# temp_new.net
KiCad netlist of a schematic drawn in EAGLE
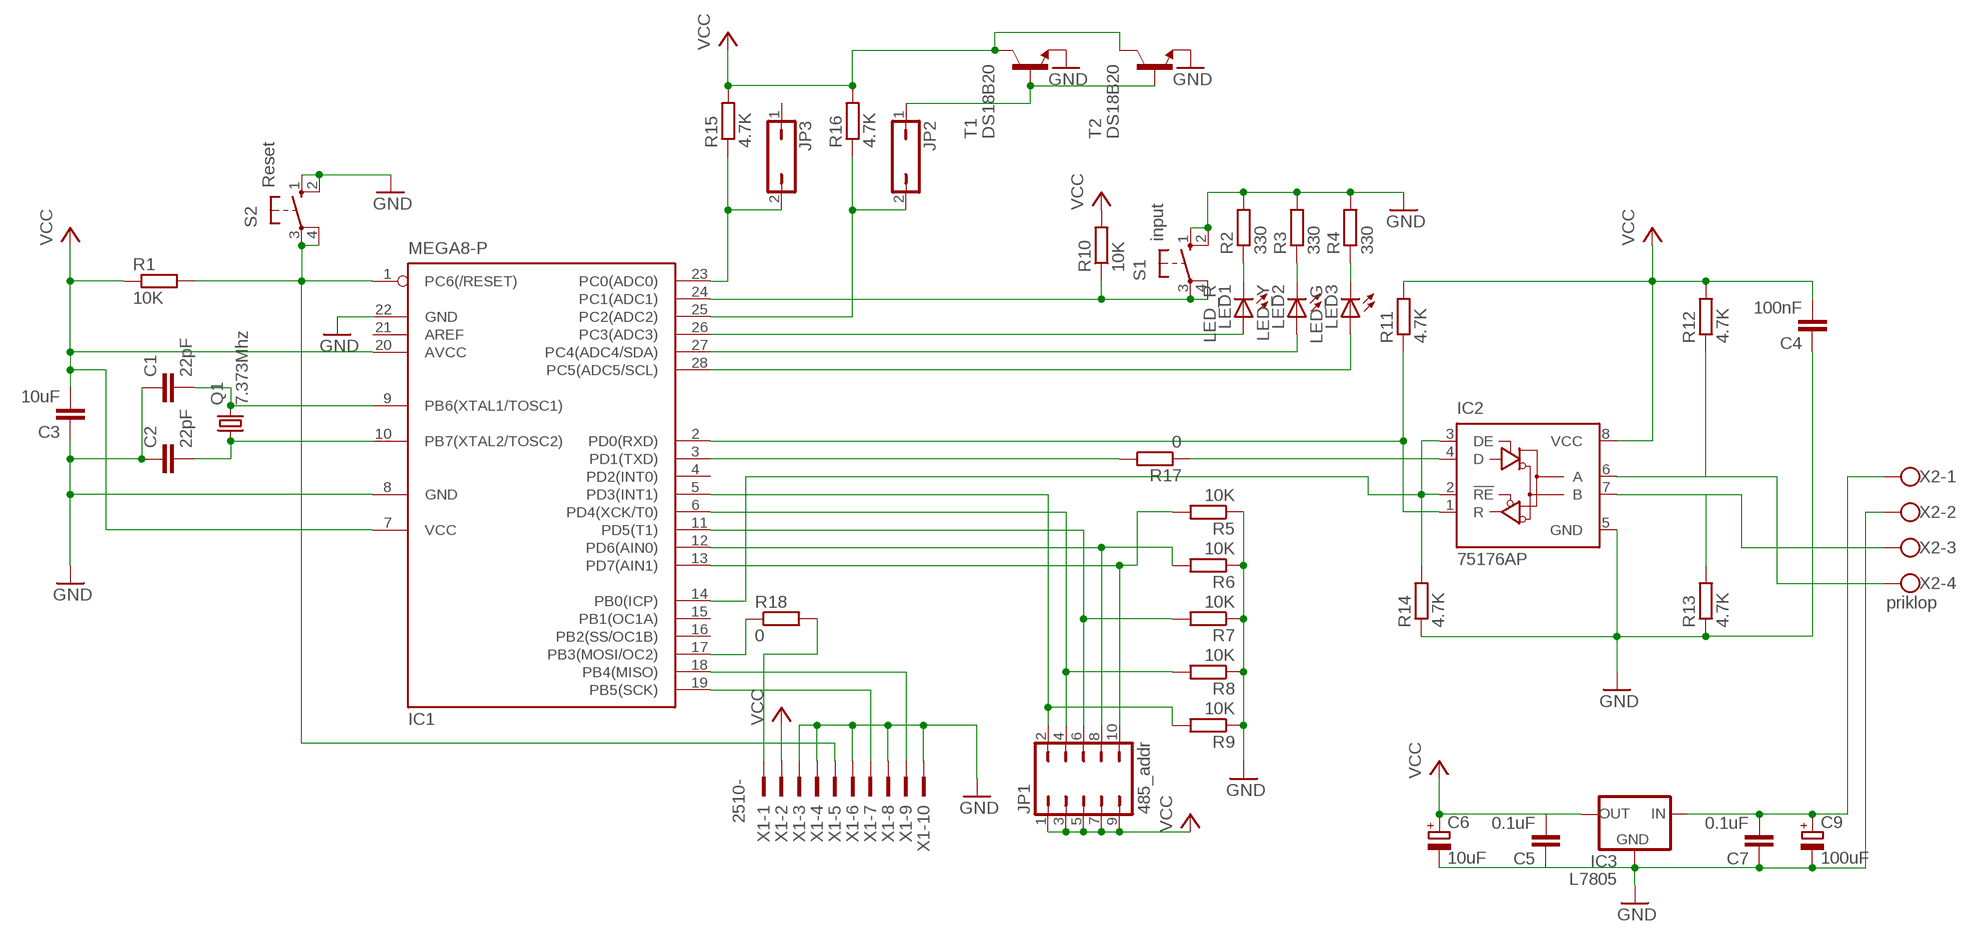
[diagram p0: schematic, sheet 1]

(export (version "E")
  (design (tool "Eeschema 10.0.6"))
  (components
    (comp (ref "C1")
      (value "22pF")
      (footprint "eagle-import:C025-030X050")
      (libsource (lib "eagle-import") (part "C-EU025-030X050"))
    )
    (comp (ref "C2")
      (value "22pF")
      (footprint "eagle-import:C025-030X050")
      (libsource (lib "eagle-import") (part "C-EU025-030X050"))
    )
    (comp (ref "C3")
      (value "10uF")
      (footprint "eagle-import:C025-030X050")
      (libsource (lib "eagle-import") (part "C-EU025-030X050"))
    )
    (comp (ref "C4")
      (value "100nF")
      (footprint "eagle-import:C025-030X050")
      (libsource (lib "eagle-import") (part "C-EU025-030X050"))
    )
    (comp (ref "C5")
      (value "0.1uF")
      (footprint "eagle-import:C025-030X050")
      (libsource (lib "eagle-import") (part "C-EU025-030X050"))
    )
    (comp (ref "C6")
      (value "10uF")
      (footprint "eagle-import:E2,5-6")
      (libsource (lib "eagle-import") (part "CPOL-EUE2.5-6"))
    )
    (comp (ref "C7")
      (value "0.1uF")
      (footprint "eagle-import:C025-030X050")
      (libsource (lib "eagle-import") (part "C-EU025-030X050"))
    )
    (comp (ref "C9")
      (value "100uF")
      (footprint "eagle-import:E5-13")
      (libsource (lib "eagle-import") (part "CPOL-EUE5-13"))
    )
    (comp (ref "IC1")
      (value "MEGA8-P")
      (footprint "eagle-import:DIL28-3")
      (libsource (lib "eagle-import") (part "MEGA8-P"))
    )
    (comp (ref "IC2")
      (value "75176AP")
      (footprint "eagle-import:DIL08")
      (libsource (lib "eagle-import") (part "75176AP"))
    )
    (comp (ref "IC3")
      (value "L7805")
      (footprint "eagle-import:78XXL")
      (libsource (lib "eagle-import") (part "78XXL"))
    )
    (comp (ref "JP1")
      (value "485_addr")
      (footprint "eagle-import:JP5Q")
      (libsource (lib "eagle-import") (part "JP5Q"))
    )
    (comp (ref "JP2")
      (value "JP1Q")
      (footprint "eagle-import:JP1")
      (libsource (lib "eagle-import") (part "JP1Q"))
    )
    (comp (ref "JP3")
      (value "JP1Q")
      (footprint "eagle-import:JP1")
      (libsource (lib "eagle-import") (part "JP1Q"))
    )
    (comp (ref "LED1")
      (value "LED_R")
      (footprint "eagle-import:LED3MM")
      (libsource (lib "eagle-import") (part "LED3MM"))
    )
    (comp (ref "LED2")
      (value "LED_Y")
      (footprint "eagle-import:LED3MM")
      (libsource (lib "eagle-import") (part "LED3MM"))
    )
    (comp (ref "LED3")
      (value "LED_G")
      (footprint "eagle-import:LED3MM")
      (libsource (lib "eagle-import") (part "LED3MM"))
    )
    (comp (ref "Q1")
      (value "7.373Mhz")
      (footprint "eagle-import:HC49_S")
      (libsource (lib "eagle-import") (part "CRYSTALHC49S"))
    )
    (comp (ref "R1")
      (value "10K")
      (footprint "eagle-import:0207_10")
      (libsource (lib "eagle-import") (part "R-EU_0207/10"))
    )
    (comp (ref "R2")
      (value "330")
      (footprint "eagle-import:0207_10")
      (libsource (lib "eagle-import") (part "R-EU_0207/10"))
    )
    (comp (ref "R3")
      (value "330")
      (footprint "eagle-import:0207_10")
      (libsource (lib "eagle-import") (part "R-EU_0207/10"))
    )
    (comp (ref "R4")
      (value "330")
      (footprint "eagle-import:0207_10")
      (libsource (lib "eagle-import") (part "R-EU_0207/10"))
    )
    (comp (ref "R5")
      (value "10K")
      (footprint "eagle-import:0207_10")
      (libsource (lib "eagle-import") (part "R-EU_0207/10"))
    )
    (comp (ref "R6")
      (value "10K")
      (footprint "eagle-import:0207_10")
      (libsource (lib "eagle-import") (part "R-EU_0207/10"))
    )
    (comp (ref "R7")
      (value "10K")
      (footprint "eagle-import:0207_10")
      (libsource (lib "eagle-import") (part "R-EU_0207/10"))
    )
    (comp (ref "R8")
      (value "10K")
      (footprint "eagle-import:0207_10")
      (libsource (lib "eagle-import") (part "R-EU_0207/10"))
    )
    (comp (ref "R9")
      (value "10K")
      (footprint "eagle-import:0207_10")
      (libsource (lib "eagle-import") (part "R-EU_0207/10"))
    )
    (comp (ref "R10")
      (value "10K")
      (footprint "eagle-import:0207_10")
      (libsource (lib "eagle-import") (part "R-EU_0207/10"))
    )
    (comp (ref "R11")
      (value "4.7K")
      (footprint "eagle-import:0207_10")
      (libsource (lib "eagle-import") (part "R-EU_0207/10"))
    )
    (comp (ref "R12")
      (value "4.7K")
      (footprint "eagle-import:0207_10")
      (libsource (lib "eagle-import") (part "R-EU_0207/10"))
    )
    (comp (ref "R13")
      (value "4.7K")
      (footprint "eagle-import:0207_10")
      (libsource (lib "eagle-import") (part "R-EU_0207/10"))
    )
    (comp (ref "R14")
      (value "4.7K")
      (footprint "eagle-import:0207_10")
      (libsource (lib "eagle-import") (part "R-EU_0207/10"))
    )
    (comp (ref "R15")
      (value "4.7K")
      (footprint "eagle-import:0207_10")
      (libsource (lib "eagle-import") (part "R-EU_0207/10"))
    )
    (comp (ref "R16")
      (value "4.7K")
      (footprint "eagle-import:0207_10")
      (libsource (lib "eagle-import") (part "R-EU_0207/10"))
    )
    (comp (ref "R17")
      (value "0")
      (footprint "eagle-import:0207_10")
      (libsource (lib "eagle-import") (part "R-EU_0207/10"))
    )
    (comp (ref "R18")
      (value "0")
      (footprint "eagle-import:0207_10")
      (libsource (lib "eagle-import") (part "R-EU_0207/10"))
    )
    (comp (ref "S1")
      (value "input")
      (footprint "eagle-import:B3F-10XX")
      (fields (field (name "MPN") "B3F-1000"))
      (libsource (lib "eagle-import") (part "10-XX"))
    )
    (comp (ref "S2")
      (value "Reset")
      (footprint "eagle-import:B3F-10XX")
      (fields (field (name "MPN") "B3F-1000"))
      (libsource (lib "eagle-import") (part "10-XX"))
    )
    (comp (ref "T1")
      (value "DS18B20")
      (footprint "eagle-import:TO92")
      (libsource (lib "eagle-import") (part "2N3565"))
    )
    (comp (ref "T2")
      (value "DS18B20")
      (footprint "eagle-import:TO92")
      (libsource (lib "eagle-import") (part "2N3565"))
    )
    (comp (ref "X1")
      (value "2510-")
      (footprint "eagle-import:PAK100_2500-10")
      (fields (field (name "MF") "3M") (field (name "MPN") "2510-6002UB"))
      (libsource (lib "eagle-import") (part "2510-"))
    )
    (comp (ref "X2")
      (value "priklop")
      (footprint "eagle-import:W237-4")
      (libsource (lib "eagle-import") (part "W237-4"))
    )
  )
  (nets
    (net (code "1") (name "GND") (class "Default")
      (node (ref "C1") (pin "1") (pinfunction "1_1") (pintype "passive"))
      (node (ref "C2") (pin "1") (pinfunction "1_1") (pintype "passive"))
      (node (ref "C3") (pin "1") (pinfunction "1_1") (pintype "passive"))
      (node (ref "C4") (pin "1") (pinfunction "1_1") (pintype "passive"))
      (node (ref "C5") (pin "1") (pinfunction "1_1") (pintype "passive"))
      (node (ref "C6") (pin "-") (pinfunction "-_-") (pintype "passive"))
      (node (ref "C7") (pin "1") (pinfunction "1_1") (pintype "passive"))
      (node (ref "C9") (pin "-") (pinfunction "-_-") (pintype "passive"))
      (node (ref "IC1") (pin "22") (pinfunction "GND_22") (pintype "power_in"))
      (node (ref "IC1") (pin "8") (pinfunction "GND_8") (pintype "power_in"))
      (node (ref "IC2") (pin "5") (pinfunction "GND_5") (pintype "power_in"))
      (node (ref "IC3") (pin "GND") (pinfunction "GND_GND") (pintype "input"))
      (node (ref "R13") (pin "1") (pinfunction "1_1") (pintype "passive"))
      (node (ref "R14") (pin "1") (pinfunction "1_1") (pintype "passive"))
      (node (ref "R2") (pin "2") (pinfunction "2_2") (pintype "passive"))
      (node (ref "R3") (pin "2") (pinfunction "2_2") (pintype "passive"))
      (node (ref "R4") (pin "2") (pinfunction "2_2") (pintype "passive"))
      (node (ref "R5") (pin "1") (pinfunction "1_1") (pintype "passive"))
      (node (ref "R6") (pin "1") (pinfunction "1_1") (pintype "passive"))
      (node (ref "R7") (pin "1") (pinfunction "1_1") (pintype "passive"))
      (node (ref "R8") (pin "1") (pinfunction "1_1") (pintype "passive"))
      (node (ref "R9") (pin "1") (pinfunction "1_1") (pintype "passive"))
      (node (ref "S1") (pin "1") (pinfunction "S_1") (pintype "passive"))
      (node (ref "S1") (pin "2") (pinfunction "S1_2") (pintype "passive"))
      (node (ref "S2") (pin "1") (pinfunction "S_1") (pintype "passive"))
      (node (ref "S2") (pin "2") (pinfunction "S1_2") (pintype "passive"))
      (node (ref "T1") (pin "3") (pinfunction "E_3") (pintype "passive"))
      (node (ref "T2") (pin "3") (pinfunction "E_3") (pintype "passive"))
      (node (ref "X1") (pin "10") (pinfunction "KL_10") (pintype "passive"))
      (node (ref "X1") (pin "3") (pinfunction "KL_3") (pintype "passive"))
      (node (ref "X1") (pin "4") (pinfunction "KL_4") (pintype "passive"))
      (node (ref "X1") (pin "6") (pinfunction "KL_6") (pintype "passive"))
      (node (ref "X1") (pin "8") (pinfunction "KL_8") (pintype "passive"))
      (node (ref "X2") (pin "2") (pinfunction "KL_2") (pintype "passive"))
    )
    (net (code "2") (name "Net-(IC1-PB0(ICP))") (class "Default")
      (node (ref "IC1") (pin "14") (pinfunction "PB0(ICP)_14") (pintype "bidirectional"))
      (node (ref "IC2") (pin "2") (pinfunction "~{RE}_2") (pintype "input"))
      (node (ref "IC2") (pin "3") (pinfunction "DE_3") (pintype "input"))
      (node (ref "R14") (pin "2") (pinfunction "2_2") (pintype "passive"))
    )
    (net (code "3") (name "Net-(IC1-PB3(MOSI{slash}OC2))") (class "Default")
      (node (ref "IC1") (pin "17") (pinfunction "PB3(MOSI/OC2)_17") (pintype "bidirectional"))
      (node (ref "R18") (pin "1") (pinfunction "1_1") (pintype "passive"))
    )
    (net (code "4") (name "Net-(IC1-PB4(MISO))") (class "Default")
      (node (ref "IC1") (pin "18") (pinfunction "PB4(MISO)_18") (pintype "bidirectional"))
      (node (ref "X1") (pin "9") (pinfunction "KL_9") (pintype "passive"))
    )
    (net (code "5") (name "Net-(IC1-PB5(SCK))") (class "Default")
      (node (ref "IC1") (pin "19") (pinfunction "PB5(SCK)_19") (pintype "bidirectional"))
      (node (ref "X1") (pin "7") (pinfunction "KL_7") (pintype "passive"))
    )
    (net (code "6") (name "Net-(IC1-PB6(XTAL1{slash}TOSC1))") (class "Default")
      (node (ref "C1") (pin "2") (pinfunction "2_2") (pintype "passive"))
      (node (ref "IC1") (pin "9") (pinfunction "PB6(XTAL1/TOSC1)_9") (pintype "bidirectional"))
      (node (ref "Q1") (pin "2") (pinfunction "2_2") (pintype "passive"))
    )
    (net (code "7") (name "Net-(IC1-PB7(XTAL2{slash}TOSC2))") (class "Default")
      (node (ref "C2") (pin "2") (pinfunction "2_2") (pintype "passive"))
      (node (ref "IC1") (pin "10") (pinfunction "PB7(XTAL2/TOSC2)_10") (pintype "bidirectional"))
      (node (ref "Q1") (pin "1") (pinfunction "1_1") (pintype "passive"))
    )
    (net (code "8") (name "Net-(IC1-PC0(ADC0))") (class "Default")
      (node (ref "IC1") (pin "23") (pinfunction "PC0(ADC0)_23") (pintype "bidirectional"))
      (node (ref "JP3") (pin "2") (pinfunction "2_2") (pintype "passive"))
      (node (ref "R15") (pin "1") (pinfunction "1_1") (pintype "passive"))
    )
    (net (code "9") (name "Net-(IC1-PC1(ADC1))") (class "Default")
      (node (ref "IC1") (pin "24") (pinfunction "PC1(ADC1)_24") (pintype "bidirectional"))
      (node (ref "R10") (pin "1") (pinfunction "1_1") (pintype "passive"))
      (node (ref "S1") (pin "3") (pinfunction "P_3") (pintype "passive"))
      (node (ref "S1") (pin "4") (pinfunction "P1_4") (pintype "passive"))
    )
    (net (code "10") (name "Net-(IC1-PC2(ADC2))") (class "Default")
      (node (ref "IC1") (pin "25") (pinfunction "PC2(ADC2)_25") (pintype "bidirectional"))
      (node (ref "JP2") (pin "2") (pinfunction "2_2") (pintype "passive"))
      (node (ref "R16") (pin "1") (pinfunction "1_1") (pintype "passive"))
    )
    (net (code "11") (name "Net-(IC1-PC3(ADC3))") (class "Default")
      (node (ref "IC1") (pin "26") (pinfunction "PC3(ADC3)_26") (pintype "bidirectional"))
      (node (ref "LED1") (pin "A") (pinfunction "A_A") (pintype "passive"))
    )
    (net (code "12") (name "Net-(IC1-PC4(ADC4{slash}SDA))") (class "Default")
      (node (ref "IC1") (pin "27") (pinfunction "PC4(ADC4/SDA)_27") (pintype "bidirectional"))
      (node (ref "LED2") (pin "A") (pinfunction "A_A") (pintype "passive"))
    )
    (net (code "13") (name "Net-(IC1-PC5(ADC5{slash}SCL))") (class "Default")
      (node (ref "IC1") (pin "28") (pinfunction "PC5(ADC5/SCL)_28") (pintype "bidirectional"))
      (node (ref "LED3") (pin "A") (pinfunction "A_A") (pintype "passive"))
    )
    (net (code "14") (name "Net-(IC1-PC6({slash}RESET))") (class "Default")
      (node (ref "IC1") (pin "1") (pinfunction "PC6(/RESET)_1") (pintype "bidirectional"))
      (node (ref "R1") (pin "2") (pinfunction "2_2") (pintype "passive"))
      (node (ref "S2") (pin "3") (pinfunction "P_3") (pintype "passive"))
      (node (ref "S2") (pin "4") (pinfunction "P1_4") (pintype "passive"))
      (node (ref "X1") (pin "5") (pinfunction "KL_5") (pintype "passive"))
    )
    (net (code "15") (name "Net-(IC1-PD0(RXD))") (class "Default")
      (node (ref "IC1") (pin "2") (pinfunction "PD0(RXD)_2") (pintype "bidirectional"))
      (node (ref "IC2") (pin "1") (pinfunction "R_1") (pintype "input"))
      (node (ref "R11") (pin "1") (pinfunction "1_1") (pintype "passive"))
    )
    (net (code "16") (name "Net-(IC1-PD1(TXD))") (class "Default")
      (node (ref "IC1") (pin "3") (pinfunction "PD1(TXD)_3") (pintype "bidirectional"))
      (node (ref "R17") (pin "2") (pinfunction "2_2") (pintype "passive"))
    )
    (net (code "17") (name "Net-(IC1-PD3(INT1))") (class "Default")
      (node (ref "IC1") (pin "5") (pinfunction "PD3(INT1)_5") (pintype "bidirectional"))
      (node (ref "JP1") (pin "2") (pinfunction "2_2") (pintype "passive"))
      (node (ref "R9") (pin "2") (pinfunction "2_2") (pintype "passive"))
    )
    (net (code "18") (name "Net-(IC1-PD4(XCK{slash}T0))") (class "Default")
      (node (ref "IC1") (pin "6") (pinfunction "PD4(XCK/T0)_6") (pintype "bidirectional"))
      (node (ref "JP1") (pin "4") (pinfunction "4_4") (pintype "passive"))
      (node (ref "R8") (pin "2") (pinfunction "2_2") (pintype "passive"))
    )
    (net (code "19") (name "Net-(IC1-PD5(T1))") (class "Default")
      (node (ref "IC1") (pin "11") (pinfunction "PD5(T1)_11") (pintype "bidirectional"))
      (node (ref "JP1") (pin "6") (pinfunction "6_6") (pintype "passive"))
      (node (ref "R7") (pin "2") (pinfunction "2_2") (pintype "passive"))
    )
    (net (code "20") (name "Net-(IC1-PD6(AIN0))") (class "Default")
      (node (ref "IC1") (pin "12") (pinfunction "PD6(AIN0)_12") (pintype "bidirectional"))
      (node (ref "JP1") (pin "8") (pinfunction "8_8") (pintype "passive"))
      (node (ref "R6") (pin "2") (pinfunction "2_2") (pintype "passive"))
    )
    (net (code "21") (name "Net-(IC1-PD7(AIN1))") (class "Default")
      (node (ref "IC1") (pin "13") (pinfunction "PD7(AIN1)_13") (pintype "bidirectional"))
      (node (ref "JP1") (pin "10") (pinfunction "10_10") (pintype "passive"))
      (node (ref "R5") (pin "2") (pinfunction "2_2") (pintype "passive"))
    )
    (net (code "22") (name "Net-(IC2-A)") (class "Default")
      (node (ref "IC2") (pin "6") (pinfunction "A_6") (pintype "output"))
      (node (ref "R12") (pin "1") (pinfunction "1_1") (pintype "passive"))
      (node (ref "X2") (pin "4") (pinfunction "KL_4") (pintype "passive"))
    )
    (net (code "23") (name "Net-(IC2-B)") (class "Default")
      (node (ref "IC2") (pin "7") (pinfunction "B_7") (pintype "output"))
      (node (ref "R13") (pin "2") (pinfunction "2_2") (pintype "passive"))
      (node (ref "X2") (pin "3") (pinfunction "KL_3") (pintype "passive"))
    )
    (net (code "24") (name "Net-(IC2-D)") (class "Default")
      (node (ref "IC2") (pin "4") (pinfunction "D_4") (pintype "input"))
      (node (ref "R17") (pin "1") (pinfunction "1_1") (pintype "passive"))
    )
    (net (code "25") (name "Net-(LED1-C)") (class "Default")
      (node (ref "LED1") (pin "K") (pinfunction "C_K") (pintype "passive"))
      (node (ref "R2") (pin "1") (pinfunction "1_1") (pintype "passive"))
    )
    (net (code "26") (name "Net-(LED2-C)") (class "Default")
      (node (ref "LED2") (pin "K") (pinfunction "C_K") (pintype "passive"))
      (node (ref "R3") (pin "1") (pinfunction "1_1") (pintype "passive"))
    )
    (net (code "27") (name "Net-(LED3-C)") (class "Default")
      (node (ref "LED3") (pin "K") (pinfunction "C_K") (pintype "passive"))
      (node (ref "R4") (pin "1") (pinfunction "1_1") (pintype "passive"))
    )
    (net (code "28") (name "Net-(T1-B)") (class "Default")
      (node (ref "JP2") (pin "1") (pinfunction "1_1") (pintype "passive"))
      (node (ref "T1") (pin "2") (pinfunction "B_2") (pintype "passive"))
      (node (ref "T2") (pin "2") (pinfunction "B_2") (pintype "passive"))
    )
    (net (code "29") (name "Net-(X1A-KL)") (class "Default")
      (node (ref "R18") (pin "2") (pinfunction "2_2") (pintype "passive"))
      (node (ref "X1") (pin "1") (pinfunction "KL_1") (pintype "passive"))
    )
    (net (code "30") (name "Net-(X2A-KL)") (class "Default")
      (node (ref "C7") (pin "2") (pinfunction "2_2") (pintype "passive"))
      (node (ref "C9") (pin "+") (pinfunction "+_+") (pintype "passive"))
      (node (ref "IC3") (pin "IN") (pinfunction "IN_IN") (pintype "input"))
      (node (ref "X2") (pin "1") (pinfunction "KL_1") (pintype "passive"))
    )
    (net (code "31") (name "VCC") (class "Default")
      (node (ref "C3") (pin "2") (pinfunction "2_2") (pintype "passive"))
      (node (ref "C4") (pin "2") (pinfunction "2_2") (pintype "passive"))
      (node (ref "C5") (pin "2") (pinfunction "2_2") (pintype "passive"))
      (node (ref "C6") (pin "+") (pinfunction "+_+") (pintype "passive"))
      (node (ref "IC1") (pin "20") (pinfunction "AVCC_20") (pintype "power_in"))
      (node (ref "IC1") (pin "7") (pinfunction "VCC_7") (pintype "power_in"))
      (node (ref "IC2") (pin "8") (pinfunction "VCC_8") (pintype "power_in"))
      (node (ref "IC3") (pin "OUT") (pinfunction "OUT_OUT") (pintype "passive"))
      (node (ref "JP1") (pin "1") (pinfunction "1_1") (pintype "passive"))
      (node (ref "JP1") (pin "3") (pinfunction "3_3") (pintype "passive"))
      (node (ref "JP1") (pin "5") (pinfunction "5_5") (pintype "passive"))
      (node (ref "JP1") (pin "7") (pinfunction "7_7") (pintype "passive"))
      (node (ref "JP1") (pin "9") (pinfunction "9_9") (pintype "passive"))
      (node (ref "R1") (pin "1") (pinfunction "1_1") (pintype "passive"))
      (node (ref "R10") (pin "2") (pinfunction "2_2") (pintype "passive"))
      (node (ref "R11") (pin "2") (pinfunction "2_2") (pintype "passive"))
      (node (ref "R12") (pin "2") (pinfunction "2_2") (pintype "passive"))
      (node (ref "R15") (pin "2") (pinfunction "2_2") (pintype "passive"))
      (node (ref "R16") (pin "2") (pinfunction "2_2") (pintype "passive"))
      (node (ref "T1") (pin "1") (pinfunction "C_1") (pintype "passive"))
      (node (ref "T2") (pin "1") (pinfunction "C_1") (pintype "passive"))
      (node (ref "X1") (pin "2") (pinfunction "KL_2") (pintype "passive"))
    )
    (net (code "32") (name "unconnected-(IC1-AREF-Pad21)") (class "Default")
      (node (ref "IC1") (pin "21") (pinfunction "AREF_21") (pintype "passive"))
    )
    (net (code "33") (name "unconnected-(IC1-PB1(OC1A)-Pad15)") (class "Default")
      (node (ref "IC1") (pin "15") (pinfunction "PB1(OC1A)_15") (pintype "bidirectional"))
    )
    (net (code "34") (name "unconnected-(IC1-PB2(SS{slash}OC1B)-Pad16)") (class "Default")
      (node (ref "IC1") (pin "16") (pinfunction "PB2(SS/OC1B)_16") (pintype "bidirectional"))
    )
    (net (code "35") (name "unconnected-(IC1-PD2(INT0)-Pad4)") (class "Default")
      (node (ref "IC1") (pin "4") (pinfunction "PD2(INT0)_4") (pintype "bidirectional"))
    )
    (net (code "36") (name "unconnected-(JP3-Pad1)") (class "Default")
      (node (ref "JP3") (pin "1") (pinfunction "1_1") (pintype "passive"))
    )
  )
)
